# Lowpass_Amplifier.net
KiCad netlist of a schematic drawn in Altium Designer
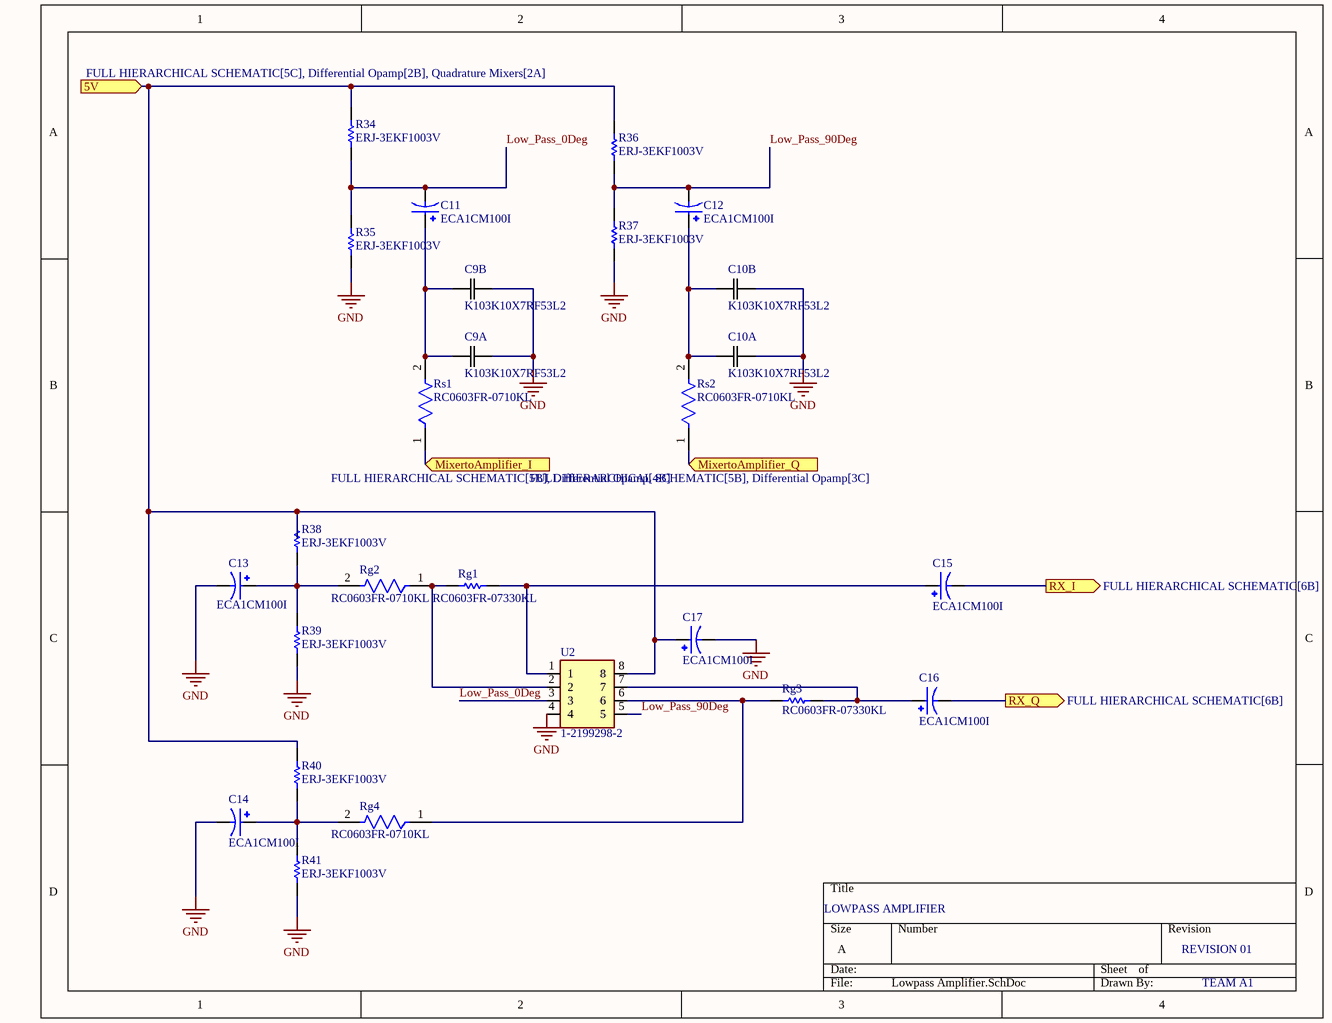
[diagram p0: Lowpass Amplifier.SchDoc]

(export (version "E")
  (design (tool "Eeschema 10.0.6"))
  (components
    (comp (ref "C9A")
      (value "K103K10X7RF53L2")
      (footprint "K103K10X7RF53L2_VIS")
      (description "No Description Available")
      (libsource (lib "K103K10X7RF53L2") (part "K103K10X7RF53L2"))
    )
    (comp (ref "C9B")
      (value "K103K10X7RF53L2")
      (footprint "K103K10X7RF53L2_VIS")
      (description "No Description Available")
      (libsource (lib "K103K10X7RF53L2") (part "K103K10X7RF53L2"))
    )
    (comp (ref "C10A")
      (value "K103K10X7RF53L2")
      (footprint "K103K10X7RF53L2_VIS")
      (description "No Description Available")
      (libsource (lib "K103K10X7RF53L2") (part "K103K10X7RF53L2"))
    )
    (comp (ref "C10B")
      (value "K103K10X7RF53L2")
      (footprint "K103K10X7RF53L2_VIS")
      (description "No Description Available")
      (libsource (lib "K103K10X7RF53L2") (part "K103K10X7RF53L2"))
    )
    (comp (ref "C11")
      (value "ECA1CM100I")
      (footprint "CAPPRD250W50D500H1100")
      (description "10ÂµF 16V Aluminum Electrolytic Capacitors Radial, Can 2000 Hrs @ 85Â°C")
      (fields (field (name "DIGI-KEY_PART_NUMBER") "P19513TB-ND") (field (name "MF") "Panasonic"))
      (libsource (lib "") (part "ECA1CM100I_2"))
    )
    (comp (ref "C12")
      (value "ECA1CM100I")
      (footprint "CAPPRD250W50D500H1100")
      (description "10ÂµF 16V Aluminum Electrolytic Capacitors Radial, Can 2000 Hrs @ 85Â°C")
      (fields (field (name "DIGI-KEY_PART_NUMBER") "P19513TB-ND") (field (name "MF") "Panasonic"))
      (libsource (lib "") (part "ECA1CM100I_2"))
    )
    (comp (ref "C13")
      (value "ECA1CM100I")
      (footprint "CAPPRD250W50D500H1100")
      (description "10ÂµF 16V Aluminum Electrolytic Capacitors Radial, Can 2000 Hrs @ 85Â°C")
      (fields (field (name "DIGI-KEY_PART_NUMBER") "P19513TB-ND") (field (name "MF") "Panasonic"))
      (libsource (lib "ECA1CM100I") (part "ECA1CM100I"))
    )
    (comp (ref "C14")
      (value "ECA1CM100I")
      (footprint "CAPPRD250W50D500H1100")
      (description "10ÂµF 16V Aluminum Electrolytic Capacitors Radial, Can 2000 Hrs @ 85Â°C")
      (fields (field (name "DIGI-KEY_PART_NUMBER") "P19513TB-ND") (field (name "MF") "Panasonic"))
      (libsource (lib "ECA1CM100I") (part "ECA1CM100I"))
    )
    (comp (ref "C15")
      (value "ECA1CM100I")
      (footprint "CAPPRD250W50D500H1100")
      (description "10ÂµF 16V Aluminum Electrolytic Capacitors Radial, Can 2000 Hrs @ 85Â°C")
      (fields (field (name "DIGI-KEY_PART_NUMBER") "P19513TB-ND") (field (name "MF") "Panasonic"))
      (libsource (lib "") (part "ECA1CM100I_1"))
    )
    (comp (ref "C16")
      (value "ECA1CM100I")
      (footprint "CAPPRD250W50D500H1100")
      (description "10ÂµF 16V Aluminum Electrolytic Capacitors Radial, Can 2000 Hrs @ 85Â°C")
      (fields (field (name "DIGI-KEY_PART_NUMBER") "P19513TB-ND") (field (name "MF") "Panasonic"))
      (libsource (lib "") (part "ECA1CM100I_1"))
    )
    (comp (ref "C17")
      (value "ECA1CM100I")
      (footprint "CAPPRD250W50D500H1100")
      (description "10ÂµF 16V Aluminum Electrolytic Capacitors Radial, Can 2000 Hrs @ 85Â°C")
      (fields (field (name "DIGI-KEY_PART_NUMBER") "P19513TB-ND") (field (name "MF") "Panasonic"))
      (libsource (lib "") (part "ECA1CM100I_1"))
    )
    (comp (ref "R34")
      (value "ERJ-3EKF1003V")
      (footprint "RESC1608X55X30ML15T15")
      (fields (field (name "MANUFACTURER") "Panasonic"))
      (libsource (lib "Altium Content Vault") (part "RES"))
    )
    (comp (ref "R35")
      (value "ERJ-3EKF1003V")
      (footprint "RESC1608X55X30ML15T15")
      (fields (field (name "MANUFACTURER") "Panasonic"))
      (libsource (lib "Altium Content Vault") (part "RES"))
    )
    (comp (ref "R36")
      (value "ERJ-3EKF1003V")
      (footprint "RESC1608X55X30ML15T15")
      (fields (field (name "MANUFACTURER") "Panasonic"))
      (libsource (lib "Altium Content Vault") (part "RES"))
    )
    (comp (ref "R37")
      (value "ERJ-3EKF1003V")
      (footprint "RESC1608X55X30ML15T15")
      (fields (field (name "MANUFACTURER") "Panasonic"))
      (libsource (lib "Altium Content Vault") (part "RES"))
    )
    (comp (ref "R38")
      (value "ERJ-3EKF1003V")
      (footprint "RESC1608X55X30ML15T15")
      (fields (field (name "MANUFACTURER") "Panasonic"))
      (libsource (lib "Altium Content Vault") (part "RES"))
    )
    (comp (ref "R39")
      (value "ERJ-3EKF1003V")
      (footprint "RESC1608X55X30ML15T15")
      (fields (field (name "MANUFACTURER") "Panasonic"))
      (libsource (lib "Altium Content Vault") (part "RES"))
    )
    (comp (ref "R40")
      (value "ERJ-3EKF1003V")
      (footprint "RESC1608X55X30ML15T15")
      (fields (field (name "MANUFACTURER") "Panasonic"))
      (libsource (lib "Altium Content Vault") (part "RES"))
    )
    (comp (ref "R41")
      (value "ERJ-3EKF1003V")
      (footprint "RESC1608X55X30ML15T15")
      (fields (field (name "MANUFACTURER") "Panasonic"))
      (libsource (lib "Altium Content Vault") (part "RES"))
    )
    (comp (ref "Rg1")
      (value "RC0603FR-07330KL")
      (footprint "RESC0603(1608)_M")
      (description "330K 0.1W 1% 0603 (1608 Metric)  SMD")
      (fields (field (name "POWER") "0.1 W") (field (name "TOLERANCE") "1 %"))
      (libsource (lib "Altium Content Vault") (part "RES"))
    )
    (comp (ref "Rg2")
      (value "RC0603FR-0710KL")
      (footprint "FP-RC0603-0_55-IPC_C")
      (description "RES 10K OHM 1% 1/10W 0603")
      (fields (field (name "TOLERANCE") "1%"))
      (libsource (lib "Altium Content Vault") (part "1029c3af85768c4190bb7ad29bc67b5"))
    )
    (comp (ref "Rg3")
      (value "RC0603FR-07330KL")
      (footprint "RESC0603(1608)_M")
      (description "330K 0.1W 1% 0603 (1608 Metric)  SMD")
      (fields (field (name "POWER") "0.1 W") (field (name "TOLERANCE") "1 %"))
      (libsource (lib "Altium Content Vault") (part "RES"))
    )
    (comp (ref "Rg4")
      (value "RC0603FR-0710KL")
      (footprint "FP-RC0603-0_55-IPC_C")
      (description "RES 10K OHM 1% 1/10W 0603")
      (fields (field (name "TOLERANCE") "1%"))
      (libsource (lib "Altium Content Vault") (part "1029c3af85768c4190bb7ad29bc67b5"))
    )
    (comp (ref "Rs1")
      (value "RC0603FR-0710KL")
      (footprint "FP-RC0603-0_55-IPC_C")
      (description "RES 10K OHM 1% 1/10W 0603")
      (fields (field (name "TOLERANCE") "1%"))
      (libsource (lib "Altium Content Vault") (part "1029c3af85768c4190bb7ad29bc67b5"))
    )
    (comp (ref "Rs2")
      (value "RC0603FR-0710KL")
      (footprint "FP-RC0603-0_55-IPC_C")
      (description "RES 10K OHM 1% 1/10W 0603")
      (fields (field (name "TOLERANCE") "1%"))
      (libsource (lib "Altium Content Vault") (part "1029c3af85768c4190bb7ad29bc67b5"))
    )
    (comp (ref "U2")
      (value "1-2199298-2")
      (footprint "TE_1-2199298-2")
      (description "8 _2 x 4_ Pos DIP, 0.3 _7.62mm_ Row Spacing Socket Tin Through Hole")
      (fields (field (name "MF") "TE Connectivity"))
      (libsource (lib "1-2199298-2") (part "1-2199298-2"))
    )
  )
  (nets
    (net (code "1") (name "/5V") (class "Default")
      (node (ref "C17") (pin "P") (pinfunction "P_P") (pintype "passive"))
      (node (ref "R34") (pin "2") (pinfunction "2_2") (pintype "passive"))
      (node (ref "R36") (pin "2") (pinfunction "2_2") (pintype "passive"))
      (node (ref "R38") (pin "2") (pinfunction "2_2") (pintype "passive"))
      (node (ref "R40") (pin "2") (pinfunction "2_2") (pintype "passive"))
      (node (ref "U2") (pin "8") (pinfunction "8_8") (pintype "passive"))
    )
    (net (code "2") (name "/Low_Pass_0Deg") (class "Default")
      (node (ref "C11") (pin "N") (pinfunction "N_N") (pintype "passive"))
      (node (ref "R34") (pin "1") (pinfunction "1_1") (pintype "passive"))
      (node (ref "R35") (pin "2") (pinfunction "2_2") (pintype "passive"))
      (node (ref "U2") (pin "3") (pinfunction "3_3") (pintype "passive"))
    )
    (net (code "3") (name "/Low_Pass_90Deg") (class "Default")
      (node (ref "C12") (pin "N") (pinfunction "N_N") (pintype "passive"))
      (node (ref "R36") (pin "1") (pinfunction "1_1") (pintype "passive"))
      (node (ref "R37") (pin "2") (pinfunction "2_2") (pintype "passive"))
      (node (ref "U2") (pin "5") (pinfunction "5_5") (pintype "passive"))
    )
    (net (code "4") (name "/MixertoAmplifier_I") (class "Default")
      (node (ref "Rs1") (pin "1") (pinfunction "1_1") (pintype "passive"))
    )
    (net (code "5") (name "/MixertoAmplifier_Q") (class "Default")
      (node (ref "Rs2") (pin "1") (pinfunction "1_1") (pintype "passive"))
    )
    (net (code "6") (name "/RX_I") (class "Default")
      (node (ref "C15") (pin "N") (pinfunction "N_N") (pintype "passive"))
    )
    (net (code "7") (name "/RX_Q") (class "Default")
      (node (ref "C16") (pin "N") (pinfunction "N_N") (pintype "passive"))
    )
    (net (code "8") (name "GND") (class "Default")
      (node (ref "C10A") (pin "2") (pinfunction "2_2") (pintype "passive"))
      (node (ref "C10B") (pin "2") (pinfunction "2_2") (pintype "passive"))
      (node (ref "C13") (pin "N") (pinfunction "N_N") (pintype "passive"))
      (node (ref "C14") (pin "N") (pinfunction "N_N") (pintype "passive"))
      (node (ref "C17") (pin "N") (pinfunction "N_N") (pintype "passive"))
      (node (ref "C9A") (pin "2") (pinfunction "2_2") (pintype "passive"))
      (node (ref "C9B") (pin "2") (pinfunction "2_2") (pintype "passive"))
      (node (ref "R35") (pin "1") (pinfunction "1_1") (pintype "passive"))
      (node (ref "R37") (pin "1") (pinfunction "1_1") (pintype "passive"))
      (node (ref "R39") (pin "1") (pinfunction "1_1") (pintype "passive"))
      (node (ref "R41") (pin "1") (pinfunction "1_1") (pintype "passive"))
      (node (ref "U2") (pin "4") (pinfunction "4_4") (pintype "passive"))
    )
    (net (code "9") (name "Net-(C10A-Pad1)") (class "Default")
      (node (ref "C10A") (pin "1") (pinfunction "1_1") (pintype "passive"))
      (node (ref "C10B") (pin "1") (pinfunction "1_1") (pintype "passive"))
      (node (ref "C12") (pin "P") (pinfunction "P_P") (pintype "passive"))
      (node (ref "Rs2") (pin "2") (pinfunction "2_2") (pintype "passive"))
    )
    (net (code "10") (name "Net-(C11-PadP)") (class "Default")
      (node (ref "C11") (pin "P") (pinfunction "P_P") (pintype "passive"))
      (node (ref "C9A") (pin "1") (pinfunction "1_1") (pintype "passive"))
      (node (ref "C9B") (pin "1") (pinfunction "1_1") (pintype "passive"))
      (node (ref "Rs1") (pin "2") (pinfunction "2_2") (pintype "passive"))
    )
    (net (code "11") (name "Net-(C13-PadP)") (class "Default")
      (node (ref "C13") (pin "P") (pinfunction "P_P") (pintype "passive"))
      (node (ref "R38") (pin "1") (pinfunction "1_1") (pintype "passive"))
      (node (ref "R39") (pin "2") (pinfunction "2_2") (pintype "passive"))
      (node (ref "Rg2") (pin "2") (pinfunction "2_2") (pintype "passive"))
    )
    (net (code "12") (name "Net-(C14-PadP)") (class "Default")
      (node (ref "C14") (pin "P") (pinfunction "P_P") (pintype "passive"))
      (node (ref "R40") (pin "1") (pinfunction "1_1") (pintype "passive"))
      (node (ref "R41") (pin "2") (pinfunction "2_2") (pintype "passive"))
      (node (ref "Rg4") (pin "2") (pinfunction "2_2") (pintype "passive"))
    )
    (net (code "13") (name "Net-(C15-PadP)") (class "Default")
      (node (ref "C15") (pin "P") (pinfunction "P_P") (pintype "passive"))
      (node (ref "Rg1") (pin "2") (pinfunction "2_2") (pintype "passive"))
      (node (ref "U2") (pin "1") (pinfunction "1_1") (pintype "passive"))
    )
    (net (code "14") (name "Net-(C16-PadP)") (class "Default")
      (node (ref "C16") (pin "P") (pinfunction "P_P") (pintype "passive"))
      (node (ref "Rg3") (pin "2") (pinfunction "2_2") (pintype "passive"))
      (node (ref "U2") (pin "7") (pinfunction "7_7") (pintype "passive"))
    )
    (net (code "15") (name "Net-(Rg1-Pad1)") (class "Default")
      (node (ref "Rg1") (pin "1") (pinfunction "1_1") (pintype "passive"))
      (node (ref "Rg2") (pin "1") (pinfunction "1_1") (pintype "passive"))
      (node (ref "U2") (pin "2") (pinfunction "2_2") (pintype "passive"))
    )
    (net (code "16") (name "Net-(Rg3-Pad1)") (class "Default")
      (node (ref "Rg3") (pin "1") (pinfunction "1_1") (pintype "passive"))
      (node (ref "Rg4") (pin "1") (pinfunction "1_1") (pintype "passive"))
      (node (ref "U2") (pin "6") (pinfunction "6_6") (pintype "passive"))
    )
  )
)
